# Xadow_Audio_v1_0.net
KiCad netlist of a schematic drawn in EAGLE
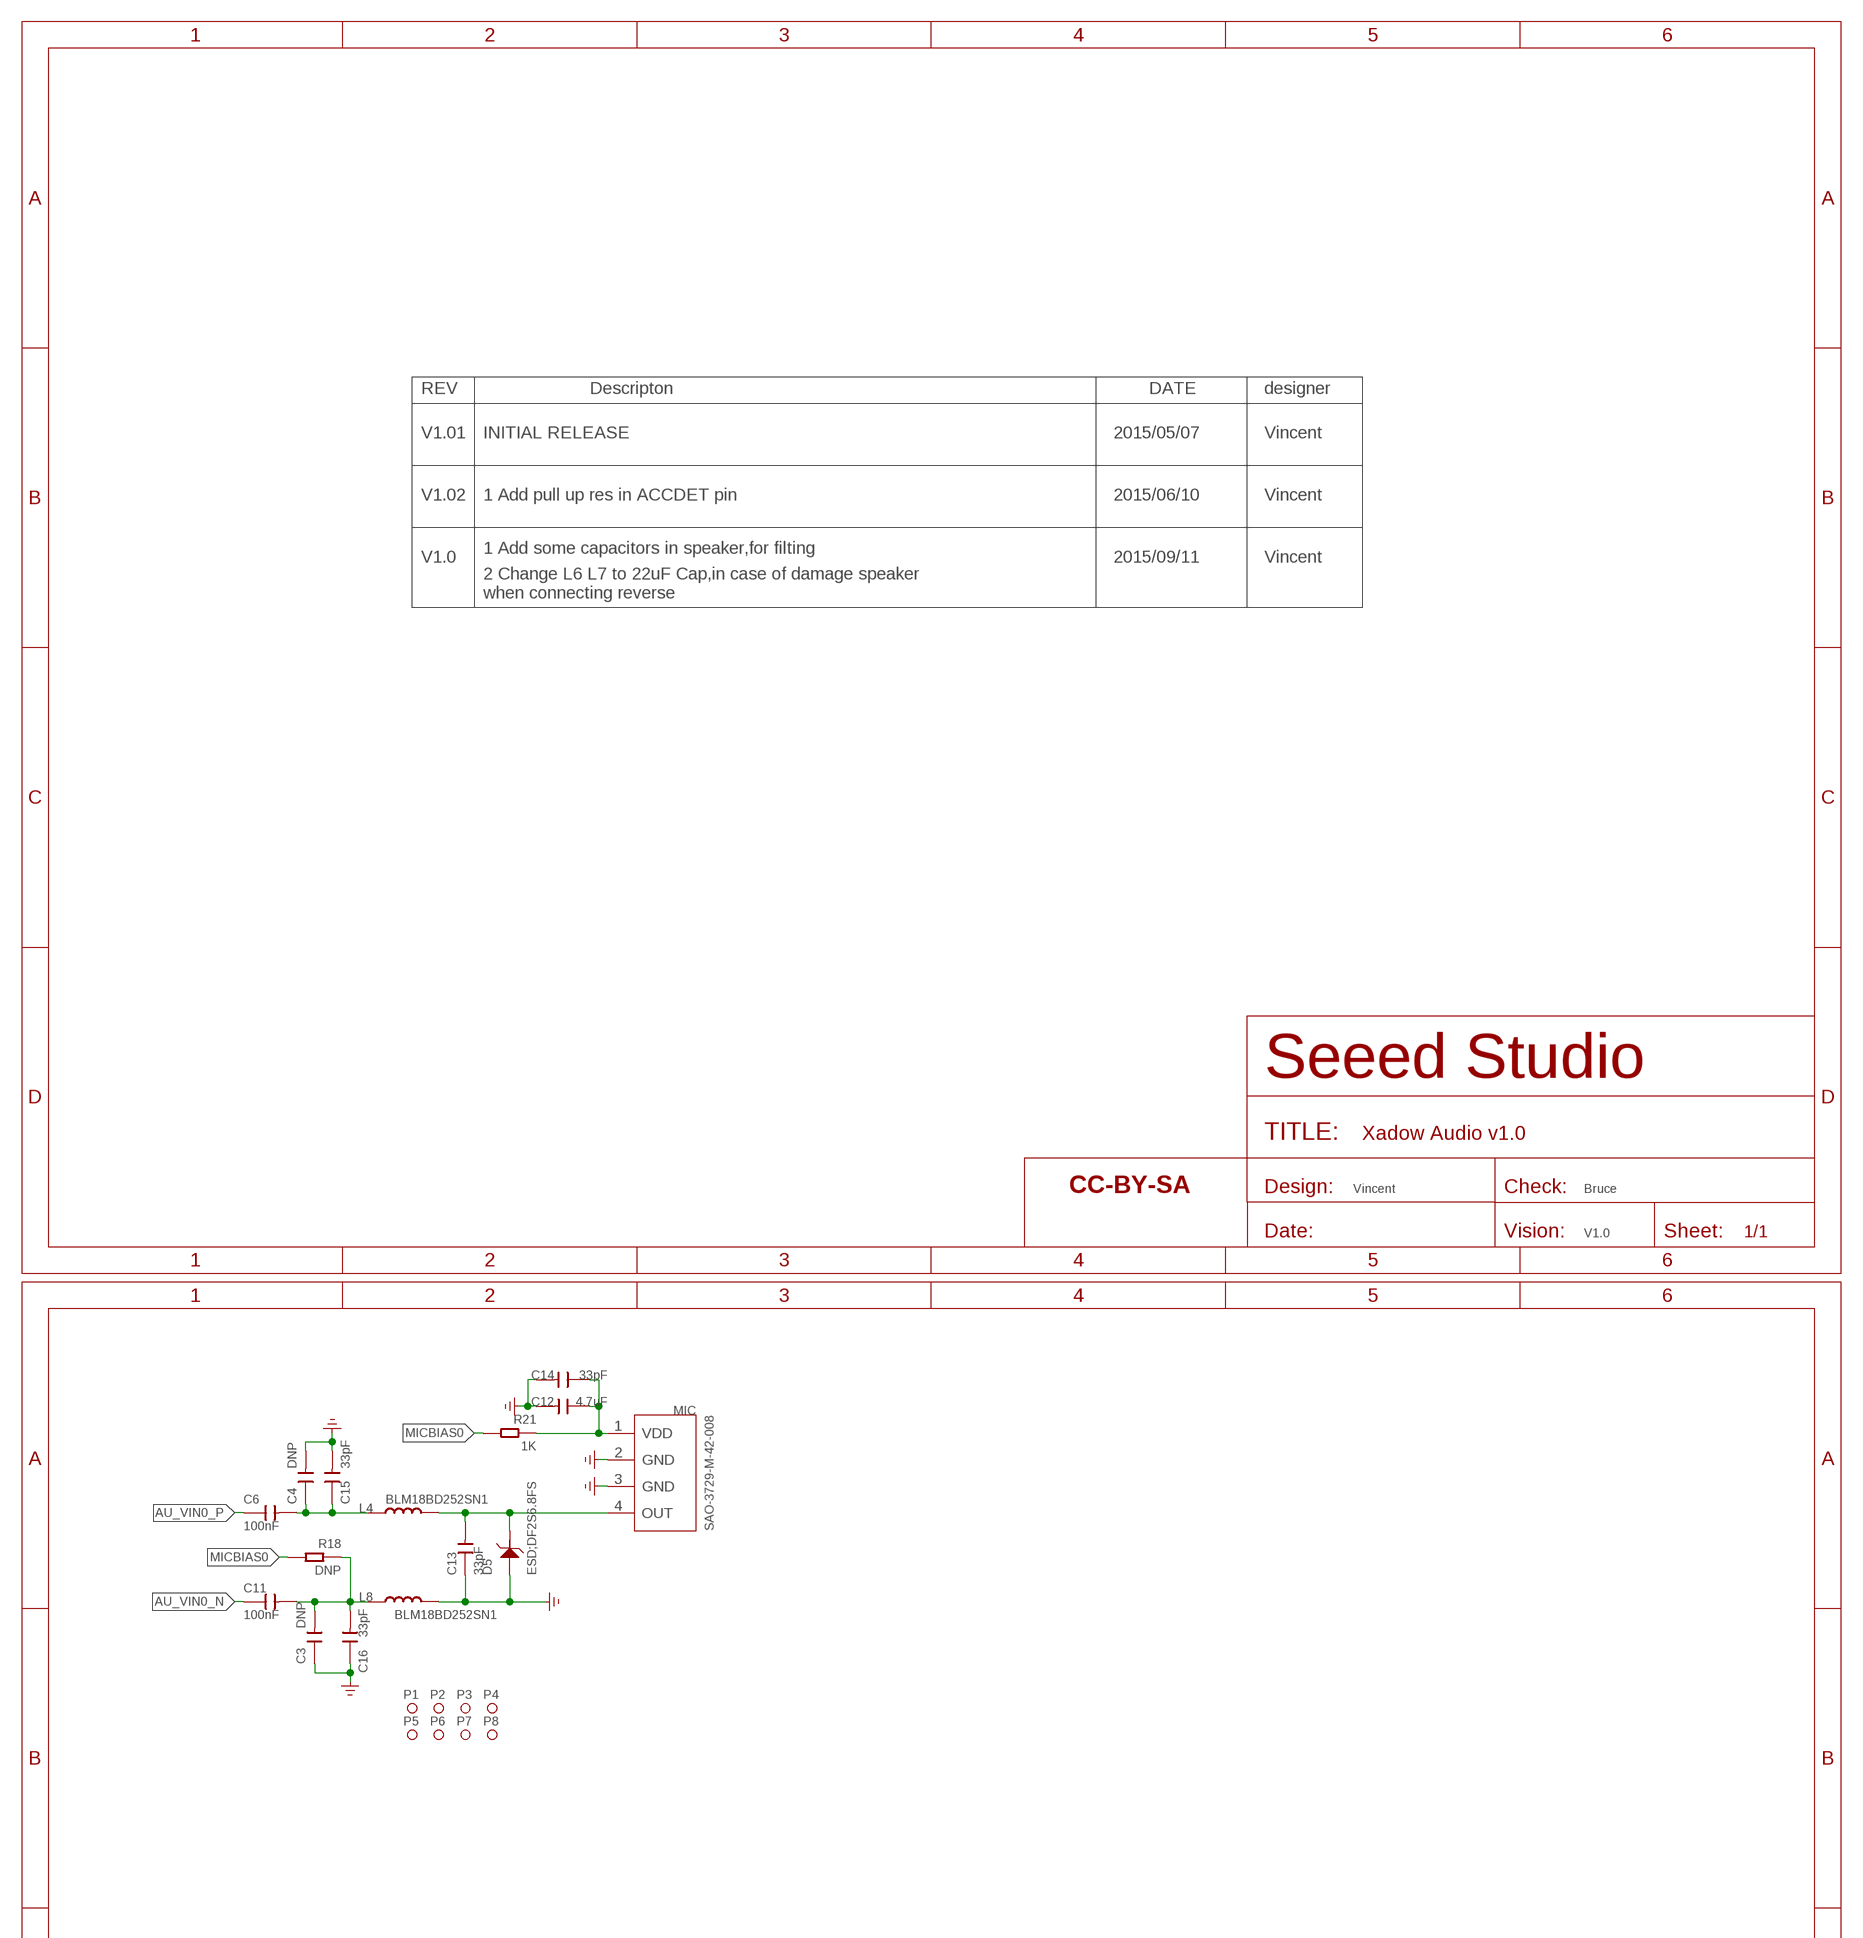
[diagram p0: schematic, sheet 1, part 1 of 2]
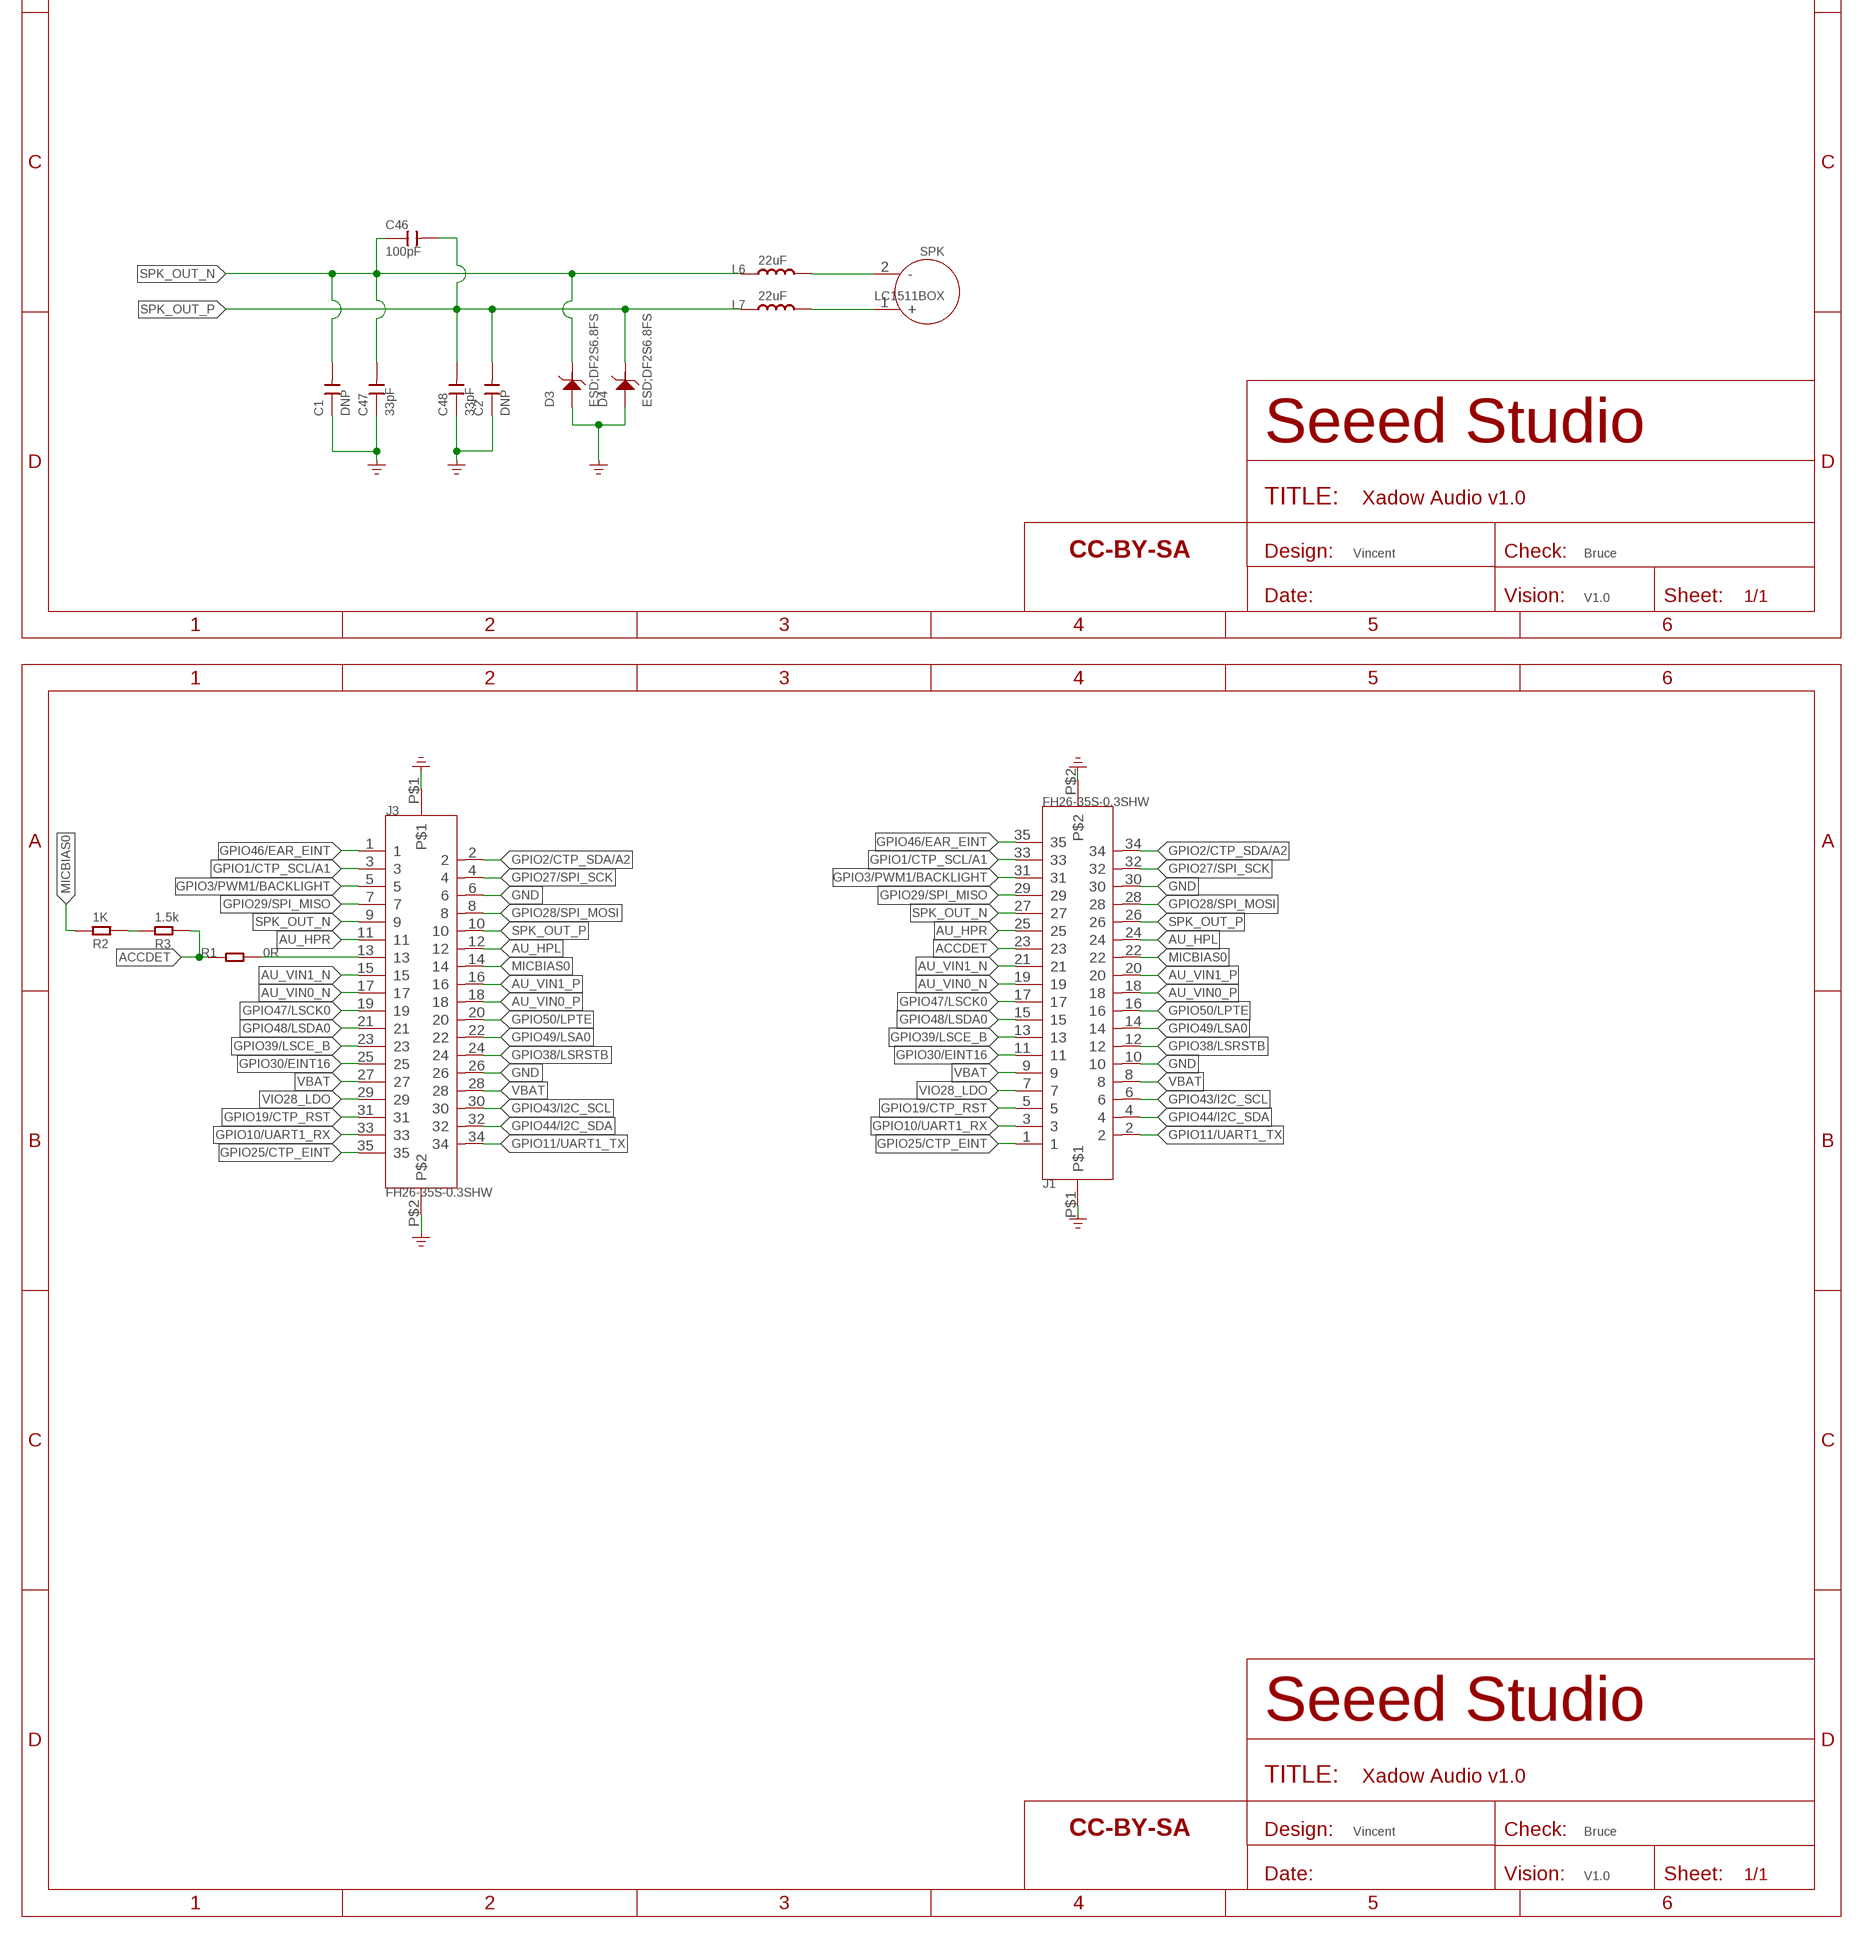
[diagram p1: schematic, sheet 1, part 2 of 2]

(export (version "E")
  (design (tool "Eeschema 10.0.6"))
  (components
    (comp (ref "C1")
      (value "DNP")
      (footprint "eagle-import:C0402")
      (libsource (lib "eagle-import") (part "CAP-0402"))
    )
    (comp (ref "C2")
      (value "DNP")
      (footprint "eagle-import:C0402")
      (libsource (lib "eagle-import") (part "CAP-0402"))
    )
    (comp (ref "C3")
      (value "DNP")
      (footprint "eagle-import:C0402")
      (libsource (lib "eagle-import") (part "CAP-0402"))
    )
    (comp (ref "C4")
      (value "DNP")
      (footprint "eagle-import:C0402")
      (libsource (lib "eagle-import") (part "CAP-0402"))
    )
    (comp (ref "C6")
      (value "100nF")
      (footprint "eagle-import:C0402")
      (libsource (lib "eagle-import") (part "CAP-0402"))
    )
    (comp (ref "C11")
      (value "100nF")
      (footprint "eagle-import:C0402")
      (libsource (lib "eagle-import") (part "CAP-0402"))
    )
    (comp (ref "C12")
      (value "4.7uF")
      (footprint "eagle-import:C0402")
      (libsource (lib "eagle-import") (part "CAP-0402"))
    )
    (comp (ref "C13")
      (value "33pF")
      (footprint "eagle-import:C0402")
      (libsource (lib "eagle-import") (part "CAP-0402"))
    )
    (comp (ref "C14")
      (value "33pF")
      (footprint "eagle-import:C0402")
      (libsource (lib "eagle-import") (part "CAP-0402"))
    )
    (comp (ref "C15")
      (value "33pF")
      (footprint "eagle-import:C0402")
      (libsource (lib "eagle-import") (part "CAP-0402"))
    )
    (comp (ref "C16")
      (value "33pF")
      (footprint "eagle-import:C0402")
      (libsource (lib "eagle-import") (part "CAP-0402"))
    )
    (comp (ref "C46")
      (value "100pF")
      (footprint "eagle-import:C0402")
      (libsource (lib "eagle-import") (part "CAP-0402"))
    )
    (comp (ref "C47")
      (value "33pF")
      (footprint "eagle-import:C0402")
      (libsource (lib "eagle-import") (part "CAP-0402"))
    )
    (comp (ref "C48")
      (value "33pF")
      (footprint "eagle-import:C0402")
      (libsource (lib "eagle-import") (part "CAP-0402"))
    )
    (comp (ref "D3")
      (value "ESD;DF2S6.8FS")
      (footprint "eagle-import:SOD-923")
      (libsource (lib "eagle-import") (part "D-ESD-2P'DF2S6.8FS'"))
    )
    (comp (ref "D4")
      (value "ESD;DF2S6.8FS")
      (footprint "eagle-import:SOD-923")
      (libsource (lib "eagle-import") (part "D-ESD-2P'DF2S6.8FS'"))
    )
    (comp (ref "D5")
      (value "ESD;DF2S6.8FS")
      (footprint "eagle-import:SOD-923")
      (libsource (lib "eagle-import") (part "D-ESD-2P'DF2S6.8FS'"))
    )
    (comp (ref "FR1")
      (value "SEEEDSTUDIO-OPEN-SCH-FRAME")
      (footprint "eagle-import:SEEEDSTUDIO-PCB-FRAME")
      (libsource (lib "eagle-import") (part "SEEEDSTUDIO-OPEN-SCH-FRAME"))
    )
    (comp (ref "J1")
      (value "FH26-35S-0.3SHW")
      (footprint "eagle-import:FPC35-SMD-0.3(FH26W)")
      (libsource (lib "eagle-import") (part "FPC-CONNECTER-35P(FH26W-35S-0.3SHW(10))"))
    )
    (comp (ref "J3")
      (value "FH26-35S-0.3SHW")
      (footprint "eagle-import:FPC35-SMD-0.3(FH26W)")
      (libsource (lib "eagle-import") (part "FPC-CONNECTER-35P(FH26W-35S-0.3SHW(10))"))
    )
    (comp (ref "L4")
      (value "BLM18BD252SN1")
      (footprint "eagle-import:L0603")
      (libsource (lib "eagle-import") (part "L'0603'"))
    )
    (comp (ref "L6")
      (value "22uF")
      (footprint "eagle-import:L0603")
      (libsource (lib "eagle-import") (part "L'0603'"))
    )
    (comp (ref "L7")
      (value "22uF")
      (footprint "eagle-import:L0603")
      (libsource (lib "eagle-import") (part "L'0603'"))
    )
    (comp (ref "L8")
      (value "BLM18BD252SN1")
      (footprint "eagle-import:L0603")
      (libsource (lib "eagle-import") (part "L'0603'"))
    )
    (comp (ref "MIC")
      (value "SAO-3729-M-42-008")
      (footprint "eagle-import:MIC4-SMD-3.76X2.95MM")
      (libsource (lib "eagle-import") (part "MIC-MSM421A3729H8-C"))
    )
    (comp (ref "P1")
      (value "MARK-1.0'ANNULAR'")
      (footprint "eagle-import:ROUND-MARK-1.0")
      (fields (field (name "PARTNO") "DNP"))
      (libsource (lib "eagle-import") (part "MARK-1.0'ANNULAR'"))
    )
    (comp (ref "P2")
      (value "MARK-1.0'ANNULAR'")
      (footprint "eagle-import:ROUND-MARK-1.0")
      (fields (field (name "PARTNO") "DNP"))
      (libsource (lib "eagle-import") (part "MARK-1.0'ANNULAR'"))
    )
    (comp (ref "P3")
      (value "MARK-1.0'ANNULAR'")
      (footprint "eagle-import:ROUND-MARK-1.0")
      (fields (field (name "PARTNO") "DNP"))
      (libsource (lib "eagle-import") (part "MARK-1.0'ANNULAR'"))
    )
    (comp (ref "P4")
      (value "MARK-1.0'ANNULAR'")
      (footprint "eagle-import:ROUND-MARK-1.0")
      (fields (field (name "PARTNO") "DNP"))
      (libsource (lib "eagle-import") (part "MARK-1.0'ANNULAR'"))
    )
    (comp (ref "P5")
      (value "MARK-1.0'ANNULAR'")
      (footprint "eagle-import:ROUND-MARK-1.0")
      (fields (field (name "PARTNO") "DNP"))
      (libsource (lib "eagle-import") (part "MARK-1.0'ANNULAR'"))
    )
    (comp (ref "P6")
      (value "MARK-1.0'ANNULAR'")
      (footprint "eagle-import:ROUND-MARK-1.0")
      (fields (field (name "PARTNO") "DNP"))
      (libsource (lib "eagle-import") (part "MARK-1.0'ANNULAR'"))
    )
    (comp (ref "P7")
      (value "MARK-1.0'ANNULAR'")
      (footprint "eagle-import:ROUND-MARK-1.0")
      (fields (field (name "PARTNO") "DNP"))
      (libsource (lib "eagle-import") (part "MARK-1.0'ANNULAR'"))
    )
    (comp (ref "P8")
      (value "MARK-1.0'ANNULAR'")
      (footprint "eagle-import:ROUND-MARK-1.0")
      (fields (field (name "PARTNO") "DNP"))
      (libsource (lib "eagle-import") (part "MARK-1.0'ANNULAR'"))
    )
    (comp (ref "R1")
      (value "0R")
      (footprint "eagle-import:R0402")
      (libsource (lib "eagle-import") (part "RES-0402"))
    )
    (comp (ref "R2")
      (value "1K")
      (footprint "eagle-import:R0402")
      (libsource (lib "eagle-import") (part "RES-0402"))
    )
    (comp (ref "R3")
      (value "1.5k")
      (footprint "eagle-import:R0402")
      (libsource (lib "eagle-import") (part "RES-0402"))
    )
    (comp (ref "R18")
      (value "DNP")
      (footprint "eagle-import:R0402")
      (libsource (lib "eagle-import") (part "RES-0402"))
    )
    (comp (ref "R21")
      (value "1K")
      (footprint "eagle-import:R0402")
      (libsource (lib "eagle-import") (part "RES-0402"))
    )
    (comp (ref "SPK")
      (value "LC1511BOX")
      (footprint "eagle-import:2P-SMD-SPEAKER")
      (libsource (lib "eagle-import") (part "SPEAKER"))
    )
    (comp (ref "U$1")
      (value "SEEEDSTUDIO-OPEN-SCH-FRAME")
      (footprint "eagle-import:SEEEDSTUDIO-PCB-FRAME")
      (libsource (lib "eagle-import") (part "SEEEDSTUDIO-OPEN-SCH-FRAME"))
    )
    (comp (ref "U$2")
      (value "SEEEDSTUDIO-OPEN-SCH-FRAME")
      (footprint "eagle-import:SEEEDSTUDIO-PCB-FRAME")
      (libsource (lib "eagle-import") (part "SEEEDSTUDIO-OPEN-SCH-FRAME"))
    )
  )
  (nets
    (net (code "1") (name "ACCDET") (class "Default")
      (node (ref "J1") (pin "23") (pinfunction "23_23") (pintype "bidirectional"))
      (node (ref "R1") (pin "2") (pinfunction "2_2") (pintype "passive"))
      (node (ref "R3") (pin "2") (pinfunction "2_2") (pintype "passive"))
    )
    (net (code "2") (name "AU_HPL") (class "Default")
      (node (ref "J1") (pin "24") (pinfunction "24_24") (pintype "bidirectional"))
      (node (ref "J3") (pin "12") (pinfunction "12_12") (pintype "bidirectional"))
    )
    (net (code "3") (name "AU_HPR") (class "Default")
      (node (ref "J1") (pin "25") (pinfunction "25_25") (pintype "bidirectional"))
      (node (ref "J3") (pin "11") (pinfunction "11_11") (pintype "bidirectional"))
    )
    (net (code "4") (name "AU_VIN0_N") (class "Default")
      (node (ref "C11") (pin "1") (pinfunction "1_1") (pintype "passive"))
      (node (ref "J1") (pin "19") (pinfunction "19_19") (pintype "bidirectional"))
      (node (ref "J3") (pin "17") (pinfunction "17_17") (pintype "bidirectional"))
    )
    (net (code "5") (name "AU_VIN0_P") (class "Default")
      (node (ref "C6") (pin "1") (pinfunction "1_1") (pintype "passive"))
      (node (ref "J1") (pin "18") (pinfunction "18_18") (pintype "bidirectional"))
      (node (ref "J3") (pin "18") (pinfunction "18_18") (pintype "bidirectional"))
    )
    (net (code "6") (name "AU_VIN1_N") (class "Default")
      (node (ref "J1") (pin "21") (pinfunction "21_21") (pintype "bidirectional"))
      (node (ref "J3") (pin "15") (pinfunction "15_15") (pintype "bidirectional"))
    )
    (net (code "7") (name "AU_VIN1_P") (class "Default")
      (node (ref "J1") (pin "20") (pinfunction "20_20") (pintype "bidirectional"))
      (node (ref "J3") (pin "16") (pinfunction "16_16") (pintype "bidirectional"))
    )
    (net (code "8") (name "GND") (class "Default")
      (node (ref "C1") (pin "1") (pinfunction "1_1") (pintype "passive"))
      (node (ref "C12") (pin "2") (pinfunction "2_2") (pintype "passive"))
      (node (ref "C13") (pin "1") (pinfunction "1_1") (pintype "passive"))
      (node (ref "C14") (pin "2") (pinfunction "2_2") (pintype "passive"))
      (node (ref "C15") (pin "2") (pinfunction "2_2") (pintype "passive"))
      (node (ref "C16") (pin "1") (pinfunction "1_1") (pintype "passive"))
      (node (ref "C2") (pin "1") (pinfunction "1_1") (pintype "passive"))
      (node (ref "C3") (pin "1") (pinfunction "1_1") (pintype "passive"))
      (node (ref "C4") (pin "2") (pinfunction "2_2") (pintype "passive"))
      (node (ref "C47") (pin "1") (pinfunction "1_1") (pintype "passive"))
      (node (ref "C48") (pin "1") (pinfunction "1_1") (pintype "passive"))
      (node (ref "D3") (pin "2") (pinfunction "1_2") (pintype "bidirectional"))
      (node (ref "D4") (pin "2") (pinfunction "1_2") (pintype "bidirectional"))
      (node (ref "D5") (pin "2") (pinfunction "1_2") (pintype "bidirectional"))
      (node (ref "J1") (pin "10") (pinfunction "10_10") (pintype "bidirectional"))
      (node (ref "J1") (pin "30") (pinfunction "30_30") (pintype "bidirectional"))
      (node (ref "J1") (pin "P$1") (pinfunction "P$1_P$1") (pintype "bidirectional"))
      (node (ref "J1") (pin "P$2") (pinfunction "P$2_P$2") (pintype "bidirectional"))
      (node (ref "J3") (pin "26") (pinfunction "26_26") (pintype "bidirectional"))
      (node (ref "J3") (pin "6") (pinfunction "6_6") (pintype "bidirectional"))
      (node (ref "J3") (pin "P$1") (pinfunction "P$1_P$1") (pintype "bidirectional"))
      (node (ref "J3") (pin "P$2") (pinfunction "P$2_P$2") (pintype "bidirectional"))
      (node (ref "L8") (pin "2") (pinfunction "2_2") (pintype "passive"))
      (node (ref "MIC") (pin "2") (pinfunction "GND_2") (pintype "bidirectional"))
      (node (ref "MIC") (pin "3") (pinfunction "GND_3") (pintype "bidirectional"))
    )
    (net (code "9") (name "GPIO1{slash}CTP_SCL{slash}A1") (class "Default")
      (node (ref "J1") (pin "33") (pinfunction "33_33") (pintype "bidirectional"))
      (node (ref "J3") (pin "3") (pinfunction "3_3") (pintype "bidirectional"))
    )
    (net (code "10") (name "GPIO2{slash}CTP_SDA{slash}A2") (class "Default")
      (node (ref "J1") (pin "34") (pinfunction "34_34") (pintype "bidirectional"))
      (node (ref "J3") (pin "2") (pinfunction "2_2") (pintype "bidirectional"))
    )
    (net (code "11") (name "GPIO3{slash}PWM1{slash}BACKLIGHT") (class "Default")
      (node (ref "J1") (pin "31") (pinfunction "31_31") (pintype "bidirectional"))
      (node (ref "J3") (pin "5") (pinfunction "5_5") (pintype "bidirectional"))
    )
    (net (code "12") (name "GPIO10{slash}UART1_RX") (class "Default")
      (node (ref "J1") (pin "3") (pinfunction "3_3") (pintype "bidirectional"))
      (node (ref "J3") (pin "33") (pinfunction "33_33") (pintype "bidirectional"))
    )
    (net (code "13") (name "GPIO11{slash}UART1_TX") (class "Default")
      (node (ref "J1") (pin "2") (pinfunction "2_2") (pintype "bidirectional"))
      (node (ref "J3") (pin "34") (pinfunction "34_34") (pintype "bidirectional"))
    )
    (net (code "14") (name "GPIO19{slash}CTP_RST") (class "Default")
      (node (ref "J1") (pin "5") (pinfunction "5_5") (pintype "bidirectional"))
      (node (ref "J3") (pin "31") (pinfunction "31_31") (pintype "bidirectional"))
    )
    (net (code "15") (name "GPIO25{slash}CTP_EINT") (class "Default")
      (node (ref "J1") (pin "1") (pinfunction "1_1") (pintype "bidirectional"))
      (node (ref "J3") (pin "35") (pinfunction "35_35") (pintype "bidirectional"))
    )
    (net (code "16") (name "GPIO27{slash}SPI_SCK") (class "Default")
      (node (ref "J1") (pin "32") (pinfunction "32_32") (pintype "bidirectional"))
      (node (ref "J3") (pin "4") (pinfunction "4_4") (pintype "bidirectional"))
    )
    (net (code "17") (name "GPIO28{slash}SPI_MOSI") (class "Default")
      (node (ref "J1") (pin "28") (pinfunction "28_28") (pintype "bidirectional"))
      (node (ref "J3") (pin "8") (pinfunction "8_8") (pintype "bidirectional"))
    )
    (net (code "18") (name "GPIO29{slash}SPI_MISO") (class "Default")
      (node (ref "J1") (pin "29") (pinfunction "29_29") (pintype "bidirectional"))
      (node (ref "J3") (pin "7") (pinfunction "7_7") (pintype "bidirectional"))
    )
    (net (code "19") (name "GPIO30{slash}EINT16") (class "Default")
      (node (ref "J1") (pin "11") (pinfunction "11_11") (pintype "bidirectional"))
      (node (ref "J3") (pin "25") (pinfunction "25_25") (pintype "bidirectional"))
    )
    (net (code "20") (name "GPIO38{slash}LSRSTB") (class "Default")
      (node (ref "J1") (pin "12") (pinfunction "12_12") (pintype "bidirectional"))
      (node (ref "J3") (pin "24") (pinfunction "24_24") (pintype "bidirectional"))
    )
    (net (code "21") (name "GPIO39{slash}LSCE_B") (class "Default")
      (node (ref "J1") (pin "13") (pinfunction "13_13") (pintype "bidirectional"))
      (node (ref "J3") (pin "23") (pinfunction "23_23") (pintype "bidirectional"))
    )
    (net (code "22") (name "GPIO43{slash}I2C_SCL") (class "Default")
      (node (ref "J1") (pin "6") (pinfunction "6_6") (pintype "bidirectional"))
      (node (ref "J3") (pin "30") (pinfunction "30_30") (pintype "bidirectional"))
    )
    (net (code "23") (name "GPIO44{slash}I2C_SDA") (class "Default")
      (node (ref "J1") (pin "4") (pinfunction "4_4") (pintype "bidirectional"))
      (node (ref "J3") (pin "32") (pinfunction "32_32") (pintype "bidirectional"))
    )
    (net (code "24") (name "GPIO46{slash}EAR_EINT") (class "Default")
      (node (ref "J1") (pin "35") (pinfunction "35_35") (pintype "bidirectional"))
      (node (ref "J3") (pin "1") (pinfunction "1_1") (pintype "bidirectional"))
    )
    (net (code "25") (name "GPIO47{slash}LSCK0") (class "Default")
      (node (ref "J1") (pin "17") (pinfunction "17_17") (pintype "bidirectional"))
      (node (ref "J3") (pin "19") (pinfunction "19_19") (pintype "bidirectional"))
    )
    (net (code "26") (name "GPIO48{slash}LSDA0") (class "Default")
      (node (ref "J1") (pin "15") (pinfunction "15_15") (pintype "bidirectional"))
      (node (ref "J3") (pin "21") (pinfunction "21_21") (pintype "bidirectional"))
    )
    (net (code "27") (name "GPIO49{slash}LSA0") (class "Default")
      (node (ref "J1") (pin "14") (pinfunction "14_14") (pintype "bidirectional"))
      (node (ref "J3") (pin "22") (pinfunction "22_22") (pintype "bidirectional"))
    )
    (net (code "28") (name "GPIO50{slash}LPTE") (class "Default")
      (node (ref "J1") (pin "16") (pinfunction "16_16") (pintype "bidirectional"))
      (node (ref "J3") (pin "20") (pinfunction "20_20") (pintype "bidirectional"))
    )
    (net (code "29") (name "MICBIAS0") (class "Default")
      (node (ref "J1") (pin "22") (pinfunction "22_22") (pintype "bidirectional"))
      (node (ref "J3") (pin "14") (pinfunction "14_14") (pintype "bidirectional"))
      (node (ref "R18") (pin "2") (pinfunction "2_2") (pintype "passive"))
      (node (ref "R2") (pin "1") (pinfunction "1_1") (pintype "passive"))
      (node (ref "R21") (pin "2") (pinfunction "2_2") (pintype "passive"))
    )
    (net (code "30") (name "Net-(C11-Pad2)") (class "Default")
      (node (ref "C11") (pin "2") (pinfunction "2_2") (pintype "passive"))
      (node (ref "C16") (pin "2") (pinfunction "2_2") (pintype "passive"))
      (node (ref "C3") (pin "2") (pinfunction "2_2") (pintype "passive"))
      (node (ref "L8") (pin "1") (pinfunction "1_1") (pintype "passive"))
      (node (ref "R18") (pin "1") (pinfunction "1_1") (pintype "passive"))
    )
    (net (code "31") (name "Net-(C15-Pad1)") (class "Default")
      (node (ref "C15") (pin "1") (pinfunction "1_1") (pintype "passive"))
      (node (ref "C4") (pin "1") (pinfunction "1_1") (pintype "passive"))
      (node (ref "C6") (pin "2") (pinfunction "2_2") (pintype "passive"))
      (node (ref "L4") (pin "1") (pinfunction "1_1") (pintype "passive"))
    )
    (net (code "32") (name "Net-(D5-2)") (class "Default")
      (node (ref "C13") (pin "2") (pinfunction "2_2") (pintype "passive"))
      (node (ref "D5") (pin "1") (pinfunction "2_1") (pintype "bidirectional"))
      (node (ref "L4") (pin "2") (pinfunction "2_2") (pintype "passive"))
      (node (ref "MIC") (pin "4") (pinfunction "OUT_4") (pintype "bidirectional"))
    )
    (net (code "33") (name "Net-(J3-Pad13)") (class "Default")
      (node (ref "J3") (pin "13") (pinfunction "13_13") (pintype "bidirectional"))
      (node (ref "R1") (pin "1") (pinfunction "1_1") (pintype "passive"))
    )
    (net (code "34") (name "Net-(MIC-VDD)") (class "Default")
      (node (ref "C12") (pin "1") (pinfunction "1_1") (pintype "passive"))
      (node (ref "C14") (pin "1") (pinfunction "1_1") (pintype "passive"))
      (node (ref "MIC") (pin "1") (pinfunction "VDD_1") (pintype "bidirectional"))
      (node (ref "R21") (pin "1") (pinfunction "1_1") (pintype "passive"))
    )
    (net (code "35") (name "Net-(R2-Pad2)") (class "Default")
      (node (ref "R2") (pin "2") (pinfunction "2_2") (pintype "passive"))
      (node (ref "R3") (pin "1") (pinfunction "1_1") (pintype "passive"))
    )
    (net (code "36") (name "Net-(SPK-+)") (class "Default")
      (node (ref "L7") (pin "2") (pinfunction "2_2") (pintype "passive"))
      (node (ref "SPK") (pin "1") (pinfunction "+_1") (pintype "passive"))
    )
    (net (code "37") (name "Net-(SPK--)") (class "Default")
      (node (ref "L6") (pin "2") (pinfunction "2_2") (pintype "passive"))
      (node (ref "SPK") (pin "2") (pinfunction "-_2") (pintype "passive"))
    )
    (net (code "38") (name "SPK_OUT_N") (class "Default")
      (node (ref "C1") (pin "2") (pinfunction "2_2") (pintype "passive"))
      (node (ref "C46") (pin "1") (pinfunction "1_1") (pintype "passive"))
      (node (ref "C47") (pin "2") (pinfunction "2_2") (pintype "passive"))
      (node (ref "D3") (pin "1") (pinfunction "2_1") (pintype "bidirectional"))
      (node (ref "J1") (pin "27") (pinfunction "27_27") (pintype "bidirectional"))
      (node (ref "J3") (pin "9") (pinfunction "9_9") (pintype "bidirectional"))
      (node (ref "L6") (pin "1") (pinfunction "1_1") (pintype "passive"))
    )
    (net (code "39") (name "SPK_OUT_P") (class "Default")
      (node (ref "C2") (pin "2") (pinfunction "2_2") (pintype "passive"))
      (node (ref "C46") (pin "2") (pinfunction "2_2") (pintype "passive"))
      (node (ref "C48") (pin "2") (pinfunction "2_2") (pintype "passive"))
      (node (ref "D4") (pin "1") (pinfunction "2_1") (pintype "bidirectional"))
      (node (ref "J1") (pin "26") (pinfunction "26_26") (pintype "bidirectional"))
      (node (ref "J3") (pin "10") (pinfunction "10_10") (pintype "bidirectional"))
      (node (ref "L7") (pin "1") (pinfunction "1_1") (pintype "passive"))
    )
    (net (code "40") (name "VBAT") (class "Default")
      (node (ref "J1") (pin "8") (pinfunction "8_8") (pintype "bidirectional"))
      (node (ref "J1") (pin "9") (pinfunction "9_9") (pintype "bidirectional"))
      (node (ref "J3") (pin "27") (pinfunction "27_27") (pintype "bidirectional"))
      (node (ref "J3") (pin "28") (pinfunction "28_28") (pintype "bidirectional"))
    )
    (net (code "41") (name "VIO28_LDO") (class "Default")
      (node (ref "J1") (pin "7") (pinfunction "7_7") (pintype "bidirectional"))
      (node (ref "J3") (pin "29") (pinfunction "29_29") (pintype "bidirectional"))
    )
  )
)
